# MM_BeanServoShield_v1_1.net
KiCad netlist of a schematic drawn in EAGLE
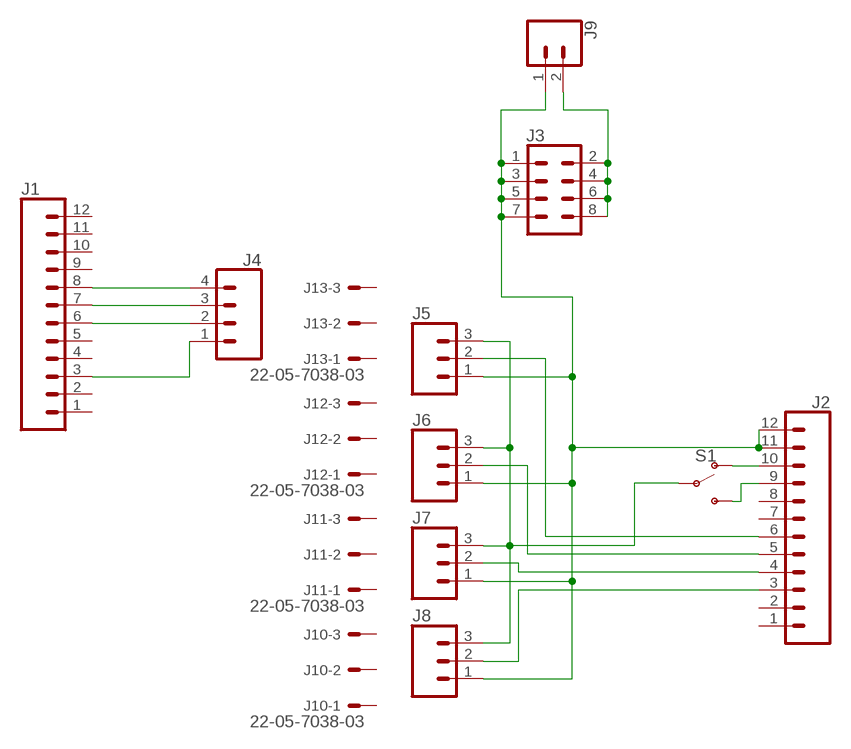
[diagram p0: schematic, sheet 1]

(export (version "E")
  (design (tool "Eeschema 10.0.6"))
  (components
    (comp (ref "J1")
      (value "CONN_12")
      (footprint "eagle-import:1X12")
      (libsource (lib "eagle-import") (part "CONN_12"))
    )
    (comp (ref "J2")
      (value "CONN_12")
      (footprint "eagle-import:1X12")
      (libsource (lib "eagle-import") (part "CONN_12"))
    )
    (comp (ref "J3")
      (value "CONN_04X2")
      (footprint "eagle-import:2X4")
      (libsource (lib "eagle-import") (part "CONN_04X2"))
    )
    (comp (ref "J4")
      (value "CONN_04")
      (footprint "eagle-import:1X04")
      (libsource (lib "eagle-import") (part "CONN_04"))
    )
    (comp (ref "J5")
      (value "CONN_03POLAR")
      (footprint "eagle-import:MOLEX-1X3")
      (libsource (lib "eagle-import") (part "CONN_03POLAR"))
    )
    (comp (ref "J6")
      (value "CONN_03POLAR")
      (footprint "eagle-import:MOLEX-1X3")
      (libsource (lib "eagle-import") (part "CONN_03POLAR"))
    )
    (comp (ref "J7")
      (value "CONN_03POLAR")
      (footprint "eagle-import:MOLEX-1X3")
      (libsource (lib "eagle-import") (part "CONN_03POLAR"))
    )
    (comp (ref "J8")
      (value "CONN_03POLAR")
      (footprint "eagle-import:MOLEX-1X3")
      (libsource (lib "eagle-import") (part "CONN_03POLAR"))
    )
    (comp (ref "J9")
      (value "CONN_02POLAR")
      (footprint "eagle-import:MOLEX-1X2")
      (libsource (lib "eagle-import") (part "CONN_02POLAR"))
    )
    (comp (ref "J10")
      (value "22-05-7038-03")
      (footprint "eagle-import:7395-03")
      (libsource (lib "eagle-import") (part "22-?-0305-7038"))
    )
    (comp (ref "J11")
      (value "22-05-7038-03")
      (footprint "eagle-import:7395-03")
      (libsource (lib "eagle-import") (part "22-?-0305-7038"))
    )
    (comp (ref "J12")
      (value "22-05-7038-03")
      (footprint "eagle-import:7395-03")
      (libsource (lib "eagle-import") (part "22-?-0305-7038"))
    )
    (comp (ref "J13")
      (value "22-05-7038-03")
      (footprint "eagle-import:7395-03")
      (libsource (lib "eagle-import") (part "22-?-0305-7038"))
    )
    (comp (ref "S1")
      (value "SWITCH-SPDT-PTH-11.6X4.0MM")
      (footprint "eagle-import:SWITCH_SPDT_PTH_11.6X4.0MM")
      (libsource (lib "eagle-import") (part "SWITCH-SPDT-PTH-11.6X4.0MM"))
    )
  )
  (nets
    (net (code "1") (name "Net-(J1-Pad3)") (class "Default")
      (node (ref "J1") (pin "3") (pinfunction "3_3") (pintype "passive"))
      (node (ref "J4") (pin "1") (pinfunction "1_1") (pintype "passive"))
    )
    (net (code "2") (name "Net-(J1-Pad6)") (class "Default")
      (node (ref "J1") (pin "6") (pinfunction "6_6") (pintype "passive"))
      (node (ref "J4") (pin "2") (pinfunction "2_2") (pintype "passive"))
    )
    (net (code "3") (name "Net-(J1-Pad7)") (class "Default")
      (node (ref "J1") (pin "7") (pinfunction "7_7") (pintype "passive"))
      (node (ref "J4") (pin "3") (pinfunction "3_3") (pintype "passive"))
    )
    (net (code "4") (name "Net-(J1-Pad8)") (class "Default")
      (node (ref "J1") (pin "8") (pinfunction "8_8") (pintype "passive"))
      (node (ref "J4") (pin "4") (pinfunction "4_4") (pintype "passive"))
    )
    (net (code "5") (name "Net-(J2-Pad3)") (class "Default")
      (node (ref "J2") (pin "3") (pinfunction "3_3") (pintype "passive"))
      (node (ref "J8") (pin "2") (pinfunction "2_2") (pintype "passive"))
    )
    (net (code "6") (name "Net-(J2-Pad4)") (class "Default")
      (node (ref "J2") (pin "4") (pinfunction "4_4") (pintype "passive"))
      (node (ref "J7") (pin "2") (pinfunction "2_2") (pintype "passive"))
    )
    (net (code "7") (name "Net-(J2-Pad5)") (class "Default")
      (node (ref "J2") (pin "5") (pinfunction "5_5") (pintype "passive"))
      (node (ref "J6") (pin "2") (pinfunction "2_2") (pintype "passive"))
    )
    (net (code "8") (name "Net-(J2-Pad6)") (class "Default")
      (node (ref "J2") (pin "6") (pinfunction "6_6") (pintype "passive"))
      (node (ref "J5") (pin "2") (pinfunction "2_2") (pintype "passive"))
    )
    (net (code "9") (name "Net-(J2-Pad11)") (class "Default")
      (node (ref "J2") (pin "11") (pinfunction "11_11") (pintype "passive"))
      (node (ref "J2") (pin "12") (pinfunction "12_12") (pintype "passive"))
      (node (ref "J3") (pin "1") (pinfunction "1_1") (pintype "passive"))
      (node (ref "J3") (pin "3") (pinfunction "3_3") (pintype "passive"))
      (node (ref "J3") (pin "5") (pinfunction "5_5") (pintype "passive"))
      (node (ref "J3") (pin "7") (pinfunction "7_7") (pintype "passive"))
      (node (ref "J5") (pin "1") (pinfunction "1_1") (pintype "passive"))
      (node (ref "J6") (pin "1") (pinfunction "1_1") (pintype "passive"))
      (node (ref "J7") (pin "1") (pinfunction "1_1") (pintype "passive"))
      (node (ref "J8") (pin "1") (pinfunction "1_1") (pintype "passive"))
      (node (ref "J9") (pin "1") (pinfunction "1_1") (pintype "passive"))
    )
    (net (code "10") (name "Net-(J3-Pad2)") (class "Default")
      (node (ref "J3") (pin "2") (pinfunction "2_2") (pintype "passive"))
      (node (ref "J3") (pin "4") (pinfunction "4_4") (pintype "passive"))
      (node (ref "J3") (pin "6") (pinfunction "6_6") (pintype "passive"))
      (node (ref "J3") (pin "8") (pinfunction "8_8") (pintype "passive"))
      (node (ref "J9") (pin "2") (pinfunction "2_2") (pintype "passive"))
    )
    (net (code "11") (name "Net-(S1-O)") (class "Default")
      (node (ref "J2") (pin "10") (pinfunction "10_10") (pintype "passive"))
      (node (ref "S1") (pin "1") (pinfunction "O_1") (pintype "passive"))
    )
    (net (code "12") (name "Net-(S1-P)") (class "Default")
      (node (ref "J5") (pin "3") (pinfunction "3_3") (pintype "passive"))
      (node (ref "J6") (pin "3") (pinfunction "3_3") (pintype "passive"))
      (node (ref "J7") (pin "3") (pinfunction "3_3") (pintype "passive"))
      (node (ref "J8") (pin "3") (pinfunction "3_3") (pintype "passive"))
      (node (ref "S1") (pin "2") (pinfunction "P_2") (pintype "passive"))
    )
    (net (code "13") (name "Net-(S1-S)") (class "Default")
      (node (ref "J2") (pin "9") (pinfunction "9_9") (pintype "passive"))
      (node (ref "S1") (pin "3") (pinfunction "S_3") (pintype "passive"))
    )
    (net (code "14") (name "unconnected-(J1-Pad1)") (class "Default")
      (node (ref "J1") (pin "1") (pinfunction "1_1") (pintype "passive"))
    )
    (net (code "15") (name "unconnected-(J1-Pad2)") (class "Default")
      (node (ref "J1") (pin "2") (pinfunction "2_2") (pintype "passive"))
    )
    (net (code "16") (name "unconnected-(J1-Pad4)") (class "Default")
      (node (ref "J1") (pin "4") (pinfunction "4_4") (pintype "passive"))
    )
    (net (code "17") (name "unconnected-(J1-Pad5)") (class "Default")
      (node (ref "J1") (pin "5") (pinfunction "5_5") (pintype "passive"))
    )
    (net (code "18") (name "unconnected-(J1-Pad9)") (class "Default")
      (node (ref "J1") (pin "9") (pinfunction "9_9") (pintype "passive"))
    )
    (net (code "19") (name "unconnected-(J1-Pad10)") (class "Default")
      (node (ref "J1") (pin "10") (pinfunction "10_10") (pintype "passive"))
    )
    (net (code "20") (name "unconnected-(J1-Pad11)") (class "Default")
      (node (ref "J1") (pin "11") (pinfunction "11_11") (pintype "passive"))
    )
    (net (code "21") (name "unconnected-(J1-Pad12)") (class "Default")
      (node (ref "J1") (pin "12") (pinfunction "12_12") (pintype "passive"))
    )
    (net (code "22") (name "unconnected-(J2-Pad1)") (class "Default")
      (node (ref "J2") (pin "1") (pinfunction "1_1") (pintype "passive"))
    )
    (net (code "23") (name "unconnected-(J2-Pad2)") (class "Default")
      (node (ref "J2") (pin "2") (pinfunction "2_2") (pintype "passive"))
    )
    (net (code "24") (name "unconnected-(J2-Pad7)") (class "Default")
      (node (ref "J2") (pin "7") (pinfunction "7_7") (pintype "passive"))
    )
    (net (code "25") (name "unconnected-(J2-Pad8)") (class "Default")
      (node (ref "J2") (pin "8") (pinfunction "8_8") (pintype "passive"))
    )
    (net (code "26") (name "unconnected-(J10A-S-Pad1)") (class "Default")
      (node (ref "J10") (pin "1") (pinfunction "S_1") (pintype "passive"))
    )
    (net (code "27") (name "unconnected-(J10B-S-Pad2)") (class "Default")
      (node (ref "J10") (pin "2") (pinfunction "S_2") (pintype "passive"))
    )
    (net (code "28") (name "unconnected-(J10C-S-Pad3)") (class "Default")
      (node (ref "J10") (pin "3") (pinfunction "S_3") (pintype "passive"))
    )
    (net (code "29") (name "unconnected-(J11A-S-Pad1)") (class "Default")
      (node (ref "J11") (pin "1") (pinfunction "S_1") (pintype "passive"))
    )
    (net (code "30") (name "unconnected-(J11B-S-Pad2)") (class "Default")
      (node (ref "J11") (pin "2") (pinfunction "S_2") (pintype "passive"))
    )
    (net (code "31") (name "unconnected-(J11C-S-Pad3)") (class "Default")
      (node (ref "J11") (pin "3") (pinfunction "S_3") (pintype "passive"))
    )
    (net (code "32") (name "unconnected-(J12A-S-Pad1)") (class "Default")
      (node (ref "J12") (pin "1") (pinfunction "S_1") (pintype "passive"))
    )
    (net (code "33") (name "unconnected-(J12B-S-Pad2)") (class "Default")
      (node (ref "J12") (pin "2") (pinfunction "S_2") (pintype "passive"))
    )
    (net (code "34") (name "unconnected-(J12C-S-Pad3)") (class "Default")
      (node (ref "J12") (pin "3") (pinfunction "S_3") (pintype "passive"))
    )
    (net (code "35") (name "unconnected-(J13A-S-Pad1)") (class "Default")
      (node (ref "J13") (pin "1") (pinfunction "S_1") (pintype "passive"))
    )
    (net (code "36") (name "unconnected-(J13B-S-Pad2)") (class "Default")
      (node (ref "J13") (pin "2") (pinfunction "S_2") (pintype "passive"))
    )
    (net (code "37") (name "unconnected-(J13C-S-Pad3)") (class "Default")
      (node (ref "J13") (pin "3") (pinfunction "S_3") (pintype "passive"))
    )
  )
)
